# 02_Mobile_Power.net
KiCad netlist of a schematic drawn in Altium Designer
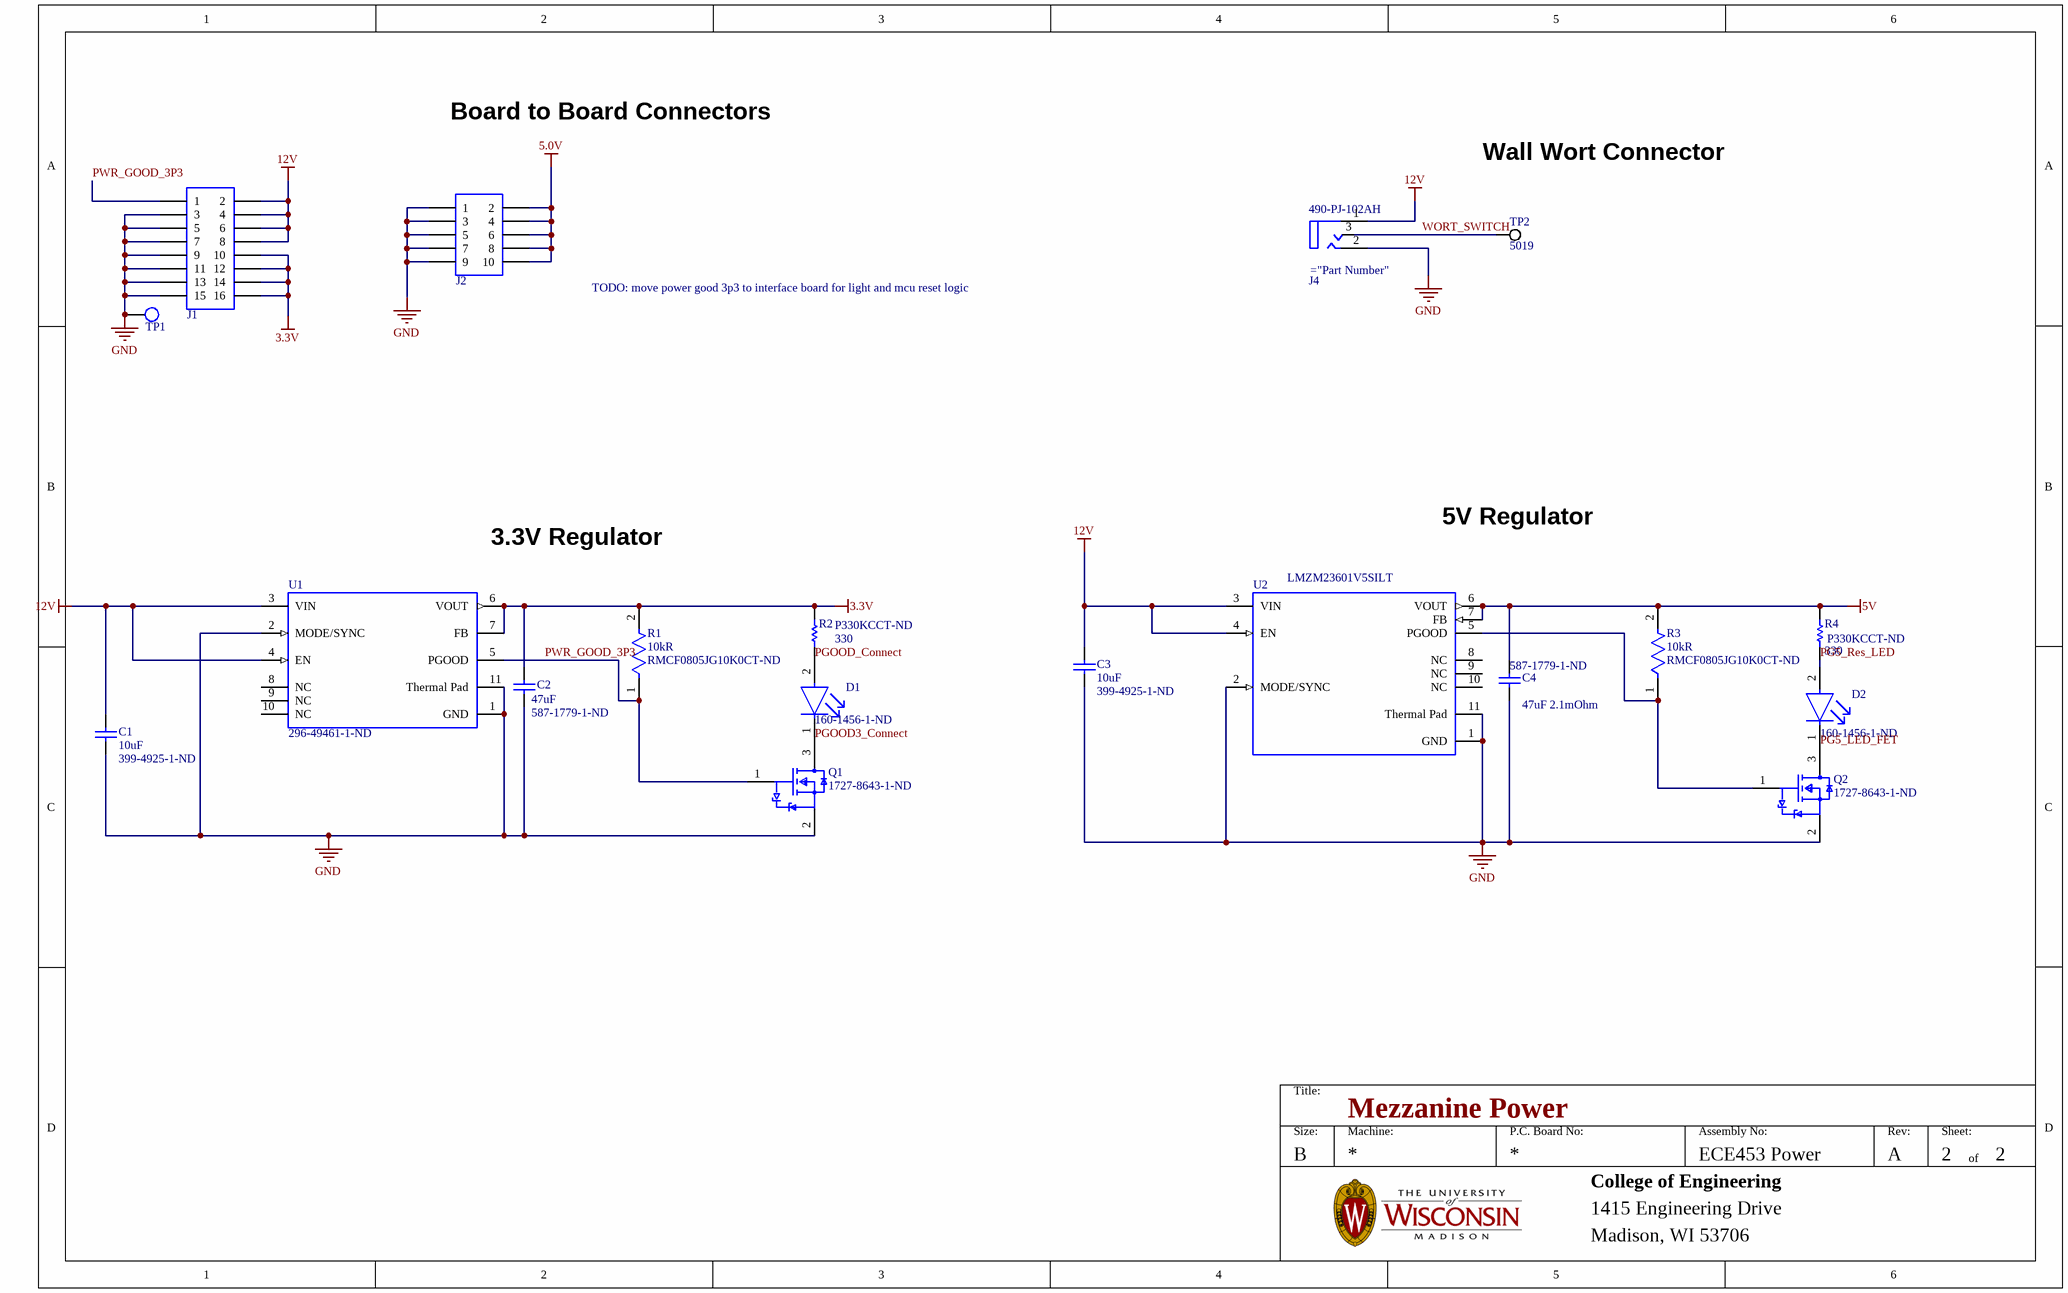
[diagram p0: 02 Mobile Power.SchDoc]

(export (version "E")
  (design (tool "Eeschema 10.0.6"))
  (components
    (comp (ref "C1")
      (value "10uF")
      (footprint "6-0805_M")
      (description "Capacitor")
      (fields
        (field (name "SUPPLIER PART NUMBER 1") "399-4925-1-ND")
        (field (name "Comment") "Cap")
        (field (name "PUBLISHER") "Altium Limited")
      )
      (libsource (lib "Miscellaneous Devices") (part "Cap"))
    )
    (comp (ref "C2")
      (value "47uF")
      (footprint "6-0805_M")
      (description "Capacitor")
      (fields
        (field (name "SUPPLIER PART NUMBER 1") "587-1779-1-ND")
        (field (name "Comment") "Cap")
        (field (name "PUBLISHER") "Altium Limited")
      )
      (libsource (lib "Miscellaneous Devices") (part "Cap"))
    )
    (comp (ref "C3")
      (value "10uF")
      (footprint "6-0805_M")
      (description "Capacitor")
      (fields
        (field (name "SUPPLIER PART NUMBER 1") "399-4925-1-ND")
        (field (name "Comment") "Cap")
        (field (name "PUBLISHER") "Altium Limited")
      )
      (libsource (lib "Miscellaneous Devices") (part "Cap"))
    )
    (comp (ref "C4")
      (value "47uF 2.1mOhm")
      (footprint "6-0805_M")
      (description "Capacitor")
      (fields
        (field (name "SUPPLIER PART NUMBER 1") "587-1779-1-ND")
        (field (name "Comment") "Cap")
        (field (name "PUBLISHER") "Altium Limited")
      )
      (libsource (lib "Miscellaneous Devices") (part "Cap"))
    )
    (comp (ref "D1")
      (value "LTST-C230KGKT")
      (footprint "Lite-On_LTST-C230KGKT_0")
      (description "LED GREEN CLEAR CHIP SMD")
      (fields
        (field (name "MANUFACTURER") "Vishay Lite-On")
        (field (name "SUPPLIER PART NUMBER 1") "160-1456-1-ND")
      )
      (libsource (lib "POWER_LIB") (part "LTST-C230KGKT"))
    )
    (comp (ref "D2")
      (value "LTST-C230KGKT")
      (footprint "Lite-On_LTST-C230KGKT_0")
      (description "LED GREEN CLEAR CHIP SMD")
      (fields
        (field (name "MANUFACTURER") "Vishay Lite-On")
        (field (name "SUPPLIER PART NUMBER 1") "160-1456-1-ND")
      )
      (libsource (lib "POWER_LIB") (part "LTST-C230KGKT"))
    )
    (comp (ref "J1")
      (value "CONN_HEADER_MALE_8x2")
      (footprint "SBH11-PBPC-D08-ST-BK")
      (description "CONN HEADER 2.54MM 16POS GOLD")
      (fields
        (field (name "MANUFACTURER") "Sullins Connector Solutions")
        (field (name "MANUFACTURER PART NUMBER") "SBH11-PBPC-D08-ST-BK")
      )
      (libsource (lib "ECE453_PWR") (part "CONN_HEADER_MALE_8x2"))
    )
    (comp (ref "J2")
      (value "CONN_HEADER_MALE_5x2")
      (footprint "SBH11-PBPC-D05-ST-BK")
      (description "CONN HEADER 2.54MM 10POS GOLD")
      (fields
        (field (name "MANUFACTURER PART NUMBER") "SBH11-PBPC-D05-ST-BK")
        (field (name "MANUFACTURER") "Sullins Connector Solutions")
      )
      (libsource (lib "ECE453_PWR") (part "CONN_HEADER_MALE_5x2"))
    )
    (comp (ref "J4")
      (value "PJ-102AH")
      (footprint "CUI_PJ-102AH_0")
      (description "2.0 x 6.5 mm, 5.0 A, Horizontal, Through Hole, Tapered Pins, Dc Power Jack Connector")
      (fields (field (name "SUPPLIER PART NUMBER 1") "490-PJ-102AH") (field (name "MANUFACTURER") "CUI"))
      (libsource (lib "ECE453-Interface") (part "PJ-102AH"))
    )
    (comp (ref "Q1")
      (value "2N7002NXAKR")
      (footprint "Nexperia_USA_Inc_SOT23_IPC_B")
      (description "2N7002NXAK - 60 V, single N-channel Trench MOSFET")
      (fields
        (field (name "MANUFACTURER") "Nexperia")
        (field (name "SUPPLIER PART NUMBER 1") "1727-8643-1-ND")
      )
      (libsource (lib "POWER_2") (part "2N7002NXAKR"))
    )
    (comp (ref "Q2")
      (value "2N7002NXAKR")
      (footprint "Nexperia_USA_Inc_SOT23_IPC_B")
      (description "2N7002NXAK - 60 V, single N-channel Trench MOSFET")
      (fields
        (field (name "MANUFACTURER") "Nexperia")
        (field (name "SUPPLIER PART NUMBER 1") "1727-8643-1-ND")
      )
      (libsource (lib "POWER_2") (part "2N7002NXAKR"))
    )
    (comp (ref "R1")
      (value "RMCF0805JG10K0")
      (footprint "0805")
      (description "Res Thick Film 0805 10K Ohm 5% 1/8W ±200ppm/°C Molded SMD Paper T/R")
      (fields
        (field (name "MANUFACTURER") "Stackpole Electronics")
        (field (name "TOLERANCE") "5%")
        (field (name "RESISTANCE") "10kR")
        (field (name "SUPPLIER PART NUMBER 1") "RMCF0805JG10K0CT-ND")
      )
      (libsource (lib "POWER_2") (part "RMCF0805JG10K0"))
    )
    (comp (ref "R2")
      (value "330")
      (footprint "6-0805_M")
      (description "SMD Chip Resistor, 0805 [2012 Metric], 330 kohm, ERJ6EN Series, 150 V, Thick Film, 125 mW")
      (fields
        (field (name "SUPPLIER PART NUMBER 1") "P330KCCT-ND")
        (field (name "MANUFACTURER") "Panasonic")
        (field (name "MANUFACTURER PART NUMBER") "ERJ6ENF3303V")
        (field (name "PUBLISHER") "Altium Limited")
      )
      (libsource (lib "Miscellaneous Devices") (part "Res1"))
    )
    (comp (ref "R3")
      (value "RMCF0805JG10K0")
      (footprint "0805")
      (description "Res Thick Film 0805 10K Ohm 5% 1/8W ±200ppm/°C Molded SMD Paper T/R")
      (fields
        (field (name "MANUFACTURER") "Stackpole Electronics")
        (field (name "TOLERANCE") "5%")
        (field (name "RESISTANCE") "10kR")
        (field (name "SUPPLIER PART NUMBER 1") "RMCF0805JG10K0CT-ND")
      )
      (libsource (lib "POWER_2") (part "RMCF0805JG10K0"))
    )
    (comp (ref "R4")
      (value "330")
      (footprint "6-0805_M")
      (description "SMD Chip Resistor, 0805 [2012 Metric], 330 kohm, ERJ6EN Series, 150 V, Thick Film, 125 mW")
      (fields
        (field (name "SUPPLIER PART NUMBER 1") "P330KCCT-ND")
        (field (name "MANUFACTURER") "Panasonic")
        (field (name "MANUFACTURER PART NUMBER") "ERJ6ENF3303V")
        (field (name "PUBLISHER") "Altium Limited")
      )
      (libsource (lib "Miscellaneous Devices") (part "Res1"))
    )
    (comp (ref "TP1")
      (value "TP_1206")
      (footprint "TP-SMC-1206")
      (description "Test Point SMD 1206")
      (libsource (lib "ECE453_PWR") (part "TP_1206"))
    )
    (comp (ref "TP2")
      (value "5019")
      (footprint "KSTN-5019_V")
      (description "Test Point, 1 Position SMD, RoHS, Tape and Reel")
      (libsource (lib "ECE453-Interface") (part "5019"))
    )
    (comp (ref "U1")
      (value "LMZM23601V3SILT")
      (footprint "Texas_Instruments_SIL0010A_MFG")
      (fields
        (field (name "MANUFACTURER") "Texas Instruments")
        (field (name "SUPPLIER PART NUMBER 1") "296-49461-1-ND")
      )
      (libsource (lib "POWER_2") (part "LMZM23601V3SILT"))
    )
    (comp (ref "U2")
      (value "LMZM23601V5SILT")
      (footprint "Texas_Instruments_SIL0010A_MFG")
      (fields (field (name "MANUFACTURER") "Texas Instruments"))
      (libsource (lib "POWER_2") (part "LMZM23601V5SILT"))
    )
  )
  (nets
    (net (code "1") (name "/PG5_LED_FET") (class "Default")
      (node (ref "D2") (pin "1") (pinfunction "C_1") (pintype "passive"))
      (node (ref "Q2") (pin "3") (pinfunction "D_3") (pintype "passive"))
    )
    (net (code "2") (name "/PG5_Res_LED") (class "Default")
      (node (ref "D2") (pin "2") (pinfunction "A_2") (pintype "passive"))
      (node (ref "R4") (pin "1") (pinfunction "1_1") (pintype "passive"))
    )
    (net (code "3") (name "/PGOOD3_Connect") (class "Default")
      (node (ref "D1") (pin "1") (pinfunction "C_1") (pintype "passive"))
      (node (ref "Q1") (pin "3") (pinfunction "D_3") (pintype "passive"))
    )
    (net (code "4") (name "/PGOOD_Connect") (class "Default")
      (node (ref "D1") (pin "2") (pinfunction "A_2") (pintype "passive"))
      (node (ref "R2") (pin "1") (pinfunction "1_1") (pintype "passive"))
    )
    (net (code "5") (name "/PWR_GOOD_3P3") (class "Default")
      (node (ref "J1") (pin "1") (pinfunction "1_1") (pintype "passive"))
      (node (ref "Q1") (pin "1") (pinfunction "G_1") (pintype "passive"))
      (node (ref "R1") (pin "1") (pinfunction "1_1") (pintype "passive"))
      (node (ref "U1") (pin "5") (pinfunction "PGOOD_5") (pintype "open_collector"))
    )
    (net (code "6") (name "/WORT_SWITCH") (class "Default")
      (node (ref "J4") (pin "3") (pinfunction "3_3") (pintype "passive"))
      (node (ref "TP2") (pin "1") (pinfunction "1_1") (pintype "passive"))
    )
    (net (code "7") (name "3.3V") (class "Default")
      (node (ref "C2") (pin "2") (pinfunction "2_2") (pintype "passive"))
      (node (ref "J1") (pin "10") (pinfunction "10_10") (pintype "passive"))
      (node (ref "J1") (pin "12") (pinfunction "12_12") (pintype "passive"))
      (node (ref "J1") (pin "14") (pinfunction "14_14") (pintype "passive"))
      (node (ref "J1") (pin "16") (pinfunction "16_16") (pintype "passive"))
      (node (ref "R1") (pin "2") (pinfunction "2_2") (pintype "passive"))
      (node (ref "R2") (pin "2") (pinfunction "2_2") (pintype "passive"))
      (node (ref "U1") (pin "6") (pinfunction "VOUT_6") (pintype "output"))
      (node (ref "U1") (pin "7") (pinfunction "FB_7") (pintype "passive"))
    )
    (net (code "8") (name "5.0V") (class "Default")
      (node (ref "J2") (pin "10") (pinfunction "10_10") (pintype "passive"))
      (node (ref "J2") (pin "2") (pinfunction "2_2") (pintype "passive"))
      (node (ref "J2") (pin "4") (pinfunction "4_4") (pintype "passive"))
      (node (ref "J2") (pin "6") (pinfunction "6_6") (pintype "passive"))
      (node (ref "J2") (pin "8") (pinfunction "8_8") (pintype "passive"))
    )
    (net (code "9") (name "5V") (class "Default")
      (node (ref "C4") (pin "2") (pinfunction "2_2") (pintype "passive"))
      (node (ref "R3") (pin "2") (pinfunction "2_2") (pintype "passive"))
      (node (ref "R4") (pin "2") (pinfunction "2_2") (pintype "passive"))
      (node (ref "U2") (pin "6") (pinfunction "VOUT_6") (pintype "output"))
      (node (ref "U2") (pin "7") (pinfunction "FB_7") (pintype "input"))
    )
    (net (code "10") (name "12V") (class "Default")
      (node (ref "C1") (pin "2") (pinfunction "2_2") (pintype "passive"))
      (node (ref "C3") (pin "2") (pinfunction "2_2") (pintype "passive"))
      (node (ref "J1") (pin "2") (pinfunction "2_2") (pintype "passive"))
      (node (ref "J1") (pin "4") (pinfunction "4_4") (pintype "passive"))
      (node (ref "J1") (pin "6") (pinfunction "6_6") (pintype "passive"))
      (node (ref "J1") (pin "8") (pinfunction "8_8") (pintype "passive"))
      (node (ref "J4") (pin "1") (pinfunction "1_1") (pintype "passive"))
      (node (ref "U1") (pin "3") (pinfunction "VIN_3") (pintype "power_in"))
      (node (ref "U1") (pin "4") (pinfunction "EN_4") (pintype "input"))
      (node (ref "U2") (pin "3") (pinfunction "VIN_3") (pintype "power_in"))
      (node (ref "U2") (pin "4") (pinfunction "EN_4") (pintype "input"))
    )
    (net (code "11") (name "GND") (class "Default")
      (node (ref "C1") (pin "1") (pinfunction "1_1") (pintype "passive"))
      (node (ref "C2") (pin "1") (pinfunction "1_1") (pintype "passive"))
      (node (ref "C3") (pin "1") (pinfunction "1_1") (pintype "passive"))
      (node (ref "C4") (pin "1") (pinfunction "1_1") (pintype "passive"))
      (node (ref "J1") (pin "11") (pinfunction "11_11") (pintype "passive"))
      (node (ref "J1") (pin "13") (pinfunction "13_13") (pintype "passive"))
      (node (ref "J1") (pin "15") (pinfunction "15_15") (pintype "passive"))
      (node (ref "J1") (pin "3") (pinfunction "3_3") (pintype "passive"))
      (node (ref "J1") (pin "5") (pinfunction "5_5") (pintype "passive"))
      (node (ref "J1") (pin "7") (pinfunction "7_7") (pintype "passive"))
      (node (ref "J1") (pin "9") (pinfunction "9_9") (pintype "passive"))
      (node (ref "J2") (pin "1") (pinfunction "1_1") (pintype "passive"))
      (node (ref "J2") (pin "3") (pinfunction "3_3") (pintype "passive"))
      (node (ref "J2") (pin "5") (pinfunction "5_5") (pintype "passive"))
      (node (ref "J2") (pin "7") (pinfunction "7_7") (pintype "passive"))
      (node (ref "J2") (pin "9") (pinfunction "9_9") (pintype "passive"))
      (node (ref "J4") (pin "2") (pinfunction "2_2") (pintype "passive"))
      (node (ref "Q1") (pin "2") (pinfunction "S_2") (pintype "passive"))
      (node (ref "Q2") (pin "2") (pinfunction "S_2") (pintype "passive"))
      (node (ref "TP1") (pin "1") (pintype "passive"))
      (node (ref "U1") (pin "1") (pinfunction "GND_1") (pintype "power_in"))
      (node (ref "U1") (pin "11") (pinfunction "Thermal_Pad_11") (pintype "power_in"))
      (node (ref "U1") (pin "2") (pinfunction "MODE/SYNC_2") (pintype "input"))
      (node (ref "U2") (pin "1") (pinfunction "GND_1") (pintype "power_in"))
      (node (ref "U2") (pin "11") (pinfunction "Thermal_Pad_11") (pintype "power_in"))
      (node (ref "U2") (pin "2") (pinfunction "MODE/SYNC_2") (pintype "input"))
    )
    (net (code "12") (name "Net-(Q2-G)") (class "Default")
      (node (ref "Q2") (pin "1") (pinfunction "G_1") (pintype "passive"))
      (node (ref "R3") (pin "1") (pinfunction "1_1") (pintype "passive"))
      (node (ref "U2") (pin "5") (pinfunction "PGOOD_5") (pintype "open_collector"))
    )
    (net (code "13") (name "unconnected-(U1-NC-Pad8)") (class "Default")
      (node (ref "U1") (pin "8") (pinfunction "NC_8") (pintype "passive"))
    )
    (net (code "14") (name "unconnected-(U1-NC-Pad9)") (class "Default")
      (node (ref "U1") (pin "9") (pinfunction "NC_9") (pintype "passive"))
    )
    (net (code "15") (name "unconnected-(U1-NC-Pad10)") (class "Default")
      (node (ref "U1") (pin "10") (pinfunction "NC_10") (pintype "passive"))
    )
    (net (code "16") (name "unconnected-(U2-NC-Pad8)") (class "Default")
      (node (ref "U2") (pin "8") (pinfunction "NC_8") (pintype "passive"))
    )
    (net (code "17") (name "unconnected-(U2-NC-Pad9)") (class "Default")
      (node (ref "U2") (pin "9") (pinfunction "NC_9") (pintype "passive"))
    )
    (net (code "18") (name "unconnected-(U2-NC-Pad10)") (class "Default")
      (node (ref "U2") (pin "10") (pinfunction "NC_10") (pintype "passive"))
    )
  )
)
